# Schematic_V0_3.net
KiCad netlist of a schematic drawn in EAGLE
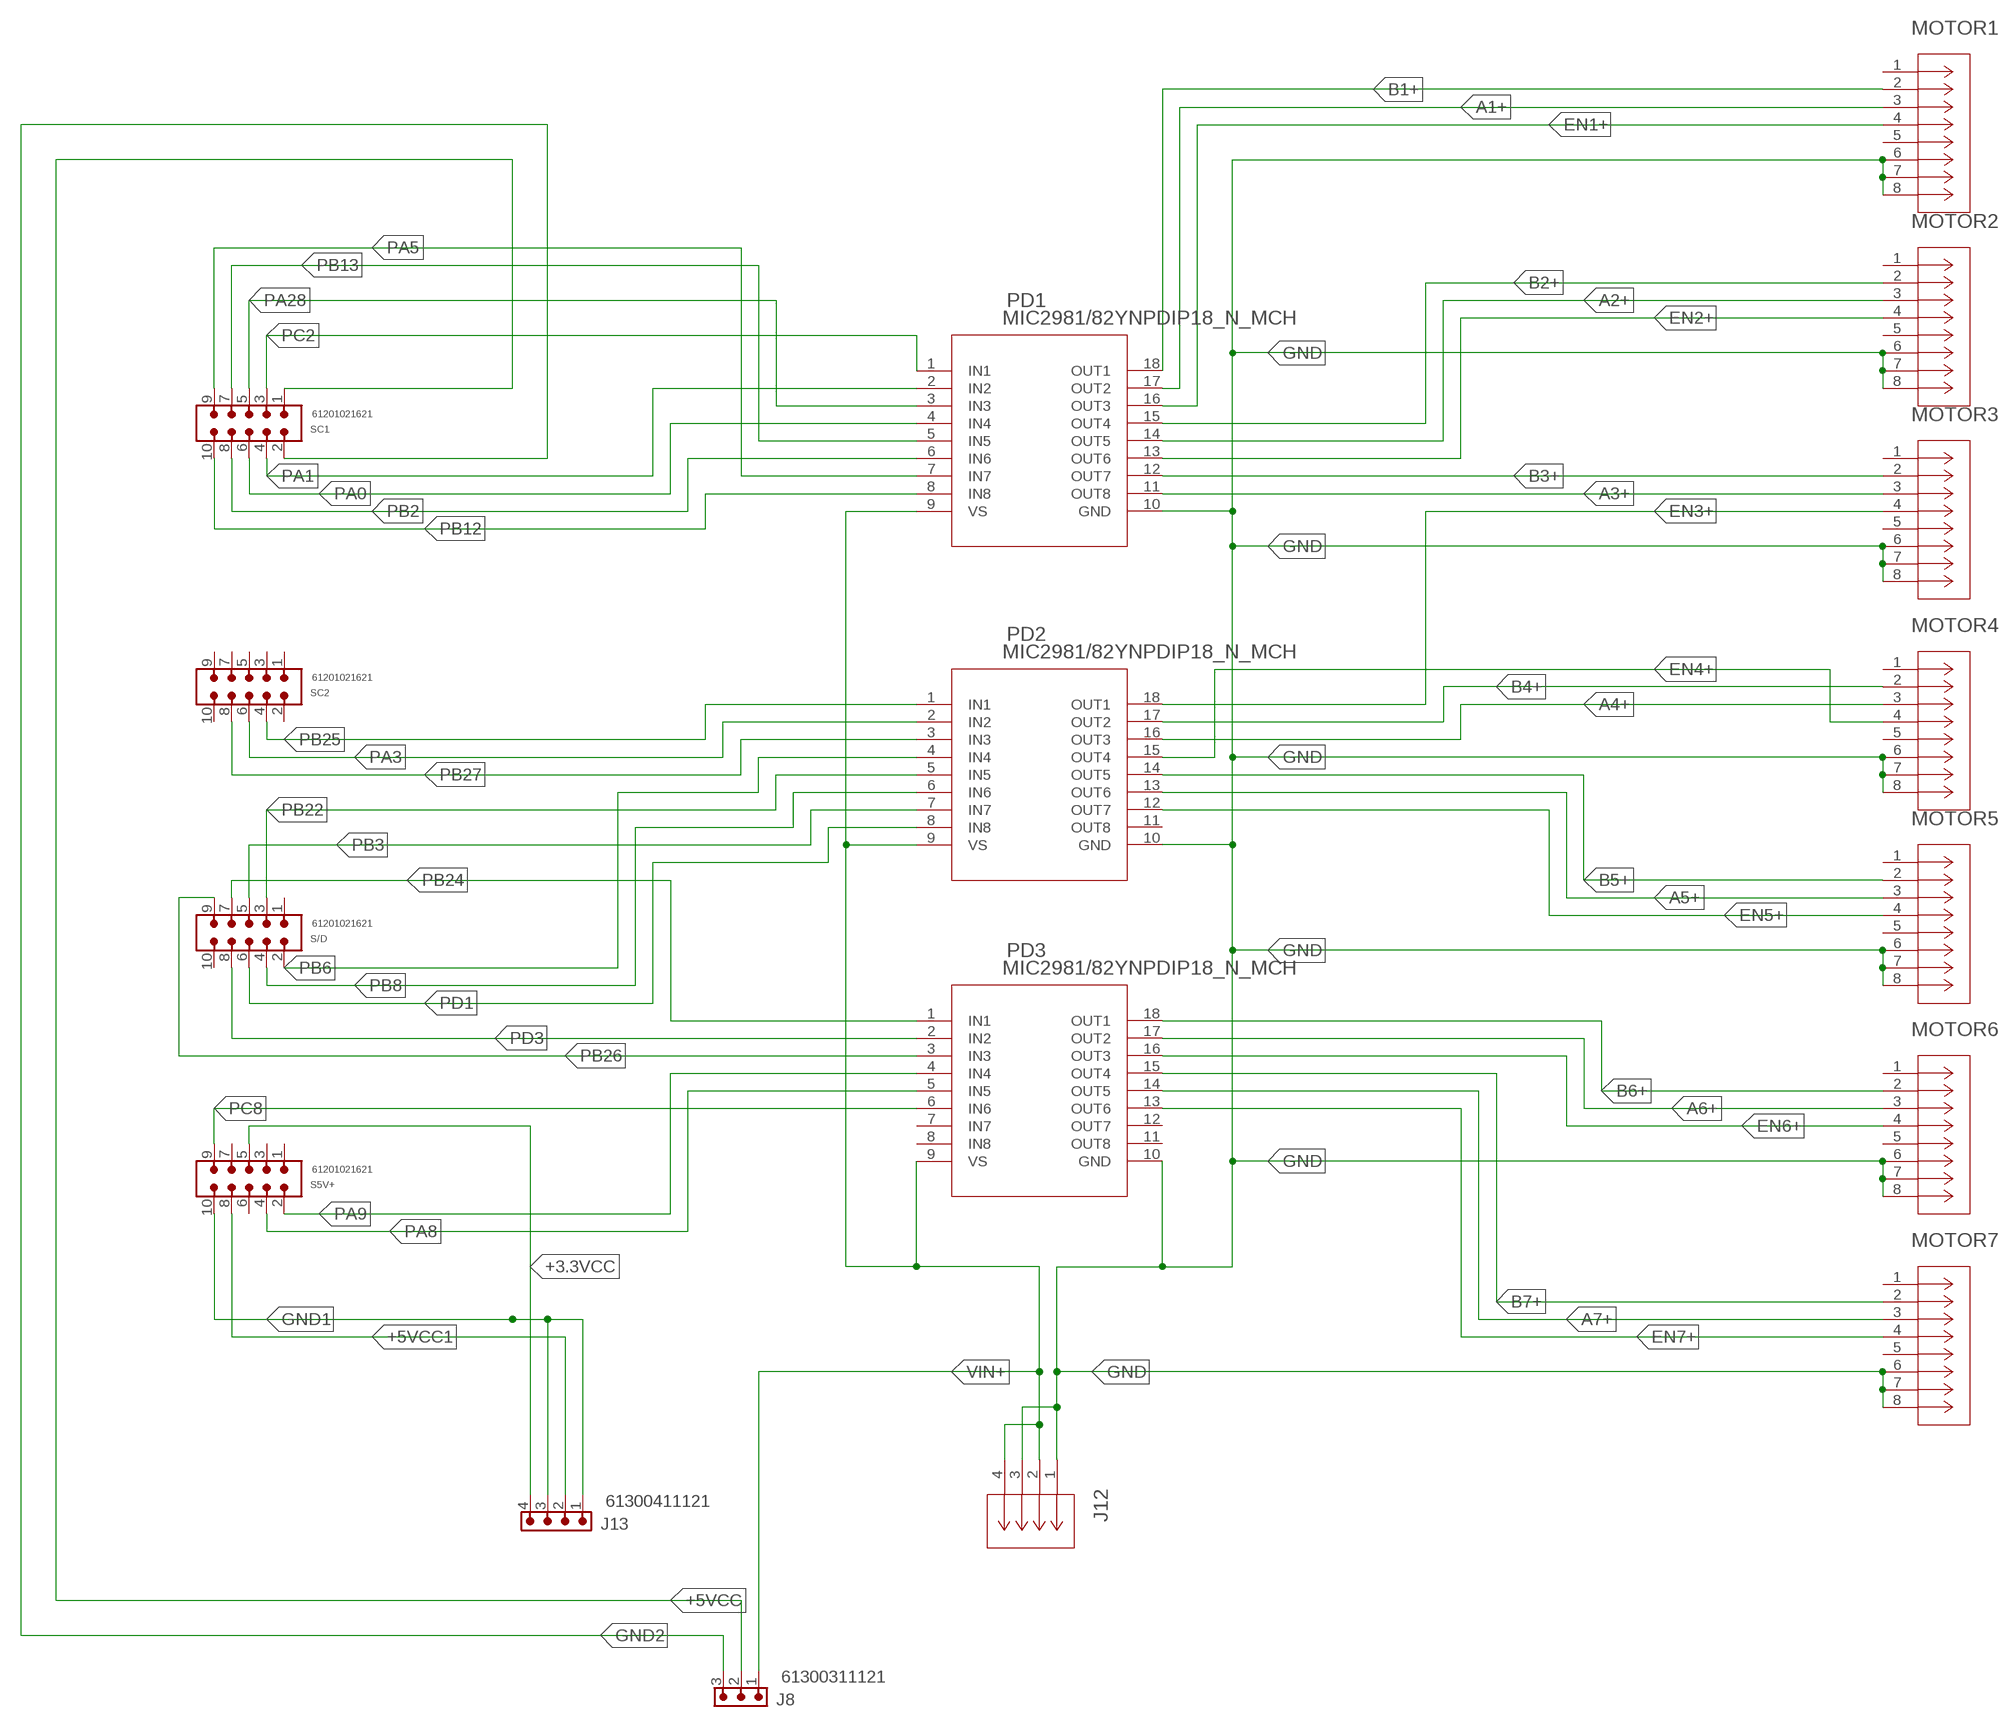
[diagram p0: schematic, sheet 1]

(export (version "E")
  (design (tool "Eeschema 10.0.6"))
  (components
    (comp (ref "J8")
      (value "61300311121")
      (footprint "eagle-import:61300311121")
      (libsource (lib "eagle-import") (part "6130XX11121_61300311121"))
    )
    (comp (ref "J12")
      (value "YK3310403000GCONN_YK331040XX00G_AMP")
      (footprint "eagle-import:CONN_YK331040XX00G_AMP")
      (fields
        (field (name "MANUFACTURER_PART_NUMBER") "YK3310403000G")
        (field (name "COPYRIGHT") "Copyright (C) 2024 Ultra Librarian. All rights reserved.")
      )
      (libsource (lib "eagle-import") (part "YK3310403000GCONN_YK331040XX00G_AMP"))
    )
    (comp (ref "J13")
      (value "61300411121")
      (footprint "eagle-import:61300411121")
      (libsource (lib "eagle-import") (part "6130XX11121_61300411121"))
    )
    (comp (ref "MOTOR1")
      (value "1724470208CON_1724470208")
      (footprint "eagle-import:CON_1724470208")
      (fields
        (field (name "MANUFACTURER_PART_NUMBER") "1724470208")
        (field (name "COPYRIGHT") "Copyright (C) 2024 Ultra Librarian. All rights reserved.")
      )
      (libsource (lib "eagle-import") (part "1724470208CON_1724470208"))
    )
    (comp (ref "MOTOR2")
      (value "1724470208CON_1724470208")
      (footprint "eagle-import:CON_1724470208")
      (fields
        (field (name "MANUFACTURER_PART_NUMBER") "1724470208")
        (field (name "COPYRIGHT") "Copyright (C) 2024 Ultra Librarian. All rights reserved.")
      )
      (libsource (lib "eagle-import") (part "1724470208CON_1724470208"))
    )
    (comp (ref "MOTOR3")
      (value "1724470208CON_1724470208")
      (footprint "eagle-import:CON_1724470208")
      (fields
        (field (name "MANUFACTURER_PART_NUMBER") "1724470208")
        (field (name "COPYRIGHT") "Copyright (C) 2024 Ultra Librarian. All rights reserved.")
      )
      (libsource (lib "eagle-import") (part "1724470208CON_1724470208"))
    )
    (comp (ref "MOTOR4")
      (value "1724470208CON_1724470208")
      (footprint "eagle-import:CON_1724470208")
      (fields
        (field (name "MANUFACTURER_PART_NUMBER") "1724470208")
        (field (name "COPYRIGHT") "Copyright (C) 2024 Ultra Librarian. All rights reserved.")
      )
      (libsource (lib "eagle-import") (part "1724470208CON_1724470208"))
    )
    (comp (ref "MOTOR5")
      (value "1724470208CON_1724470208")
      (footprint "eagle-import:CON_1724470208")
      (fields
        (field (name "MANUFACTURER_PART_NUMBER") "1724470208")
        (field (name "COPYRIGHT") "Copyright (C) 2024 Ultra Librarian. All rights reserved.")
      )
      (libsource (lib "eagle-import") (part "1724470208CON_1724470208"))
    )
    (comp (ref "MOTOR6")
      (value "1724470208CON_1724470208")
      (footprint "eagle-import:CON_1724470208")
      (fields
        (field (name "MANUFACTURER_PART_NUMBER") "1724470208")
        (field (name "COPYRIGHT") "Copyright (C) 2024 Ultra Librarian. All rights reserved.")
      )
      (libsource (lib "eagle-import") (part "1724470208CON_1724470208"))
    )
    (comp (ref "MOTOR7")
      (value "1724470208CON_1724470208")
      (footprint "eagle-import:CON_1724470208")
      (fields
        (field (name "MANUFACTURER_PART_NUMBER") "1724470208")
        (field (name "COPYRIGHT") "Copyright (C) 2024 Ultra Librarian. All rights reserved.")
      )
      (libsource (lib "eagle-import") (part "1724470208CON_1724470208"))
    )
    (comp (ref "PD1")
      (value "MIC2981/82YNPDIP18_N_MCH")
      (footprint "eagle-import:PDIP18_N_MCH")
      (fields
        (field (name "MANUFACTURER_PART_NUMBER") "MIC2981/82YN")
        (field (name "COPYRIGHT") "Copyright (C) 2024 Ultra Librarian. All rights reserved.")
      )
      (libsource (lib "eagle-import") (part "MIC2981/82YNPDIP18_N_MCH"))
    )
    (comp (ref "PD2")
      (value "MIC2981/82YNPDIP18_N_MCH")
      (footprint "eagle-import:PDIP18_N_MCH")
      (fields
        (field (name "MANUFACTURER_PART_NUMBER") "MIC2981/82YN")
        (field (name "COPYRIGHT") "Copyright (C) 2024 Ultra Librarian. All rights reserved.")
      )
      (libsource (lib "eagle-import") (part "MIC2981/82YNPDIP18_N_MCH"))
    )
    (comp (ref "PD3")
      (value "MIC2981/82YNPDIP18_N_MCH")
      (footprint "eagle-import:PDIP18_N_MCH")
      (fields
        (field (name "MANUFACTURER_PART_NUMBER") "MIC2981/82YN")
        (field (name "COPYRIGHT") "Copyright (C) 2024 Ultra Librarian. All rights reserved.")
      )
      (libsource (lib "eagle-import") (part "MIC2981/82YNPDIP18_N_MCH"))
    )
    (comp (ref "S/D")
      (value "61201021621")
      (footprint "eagle-import:61201021621")
      (libsource (lib "eagle-import") (part "6120XX21621_61201021621"))
    )
    (comp (ref "S5V+")
      (value "61201021621")
      (footprint "eagle-import:61201021621")
      (libsource (lib "eagle-import") (part "6120XX21621_61201021621"))
    )
    (comp (ref "SC1")
      (value "61201021621")
      (footprint "eagle-import:61201021621")
      (libsource (lib "eagle-import") (part "6120XX21621_61201021621"))
    )
    (comp (ref "SC2")
      (value "61201021621")
      (footprint "eagle-import:61201021621")
      (libsource (lib "eagle-import") (part "6120XX21621_61201021621"))
    )
  )
  (nets
    (net (code "1") (name "+3.3VCC") (class "Default")
      (node (ref "J13") (pin "4") (pinfunction "4_4") (pintype "passive"))
      (node (ref "S5V+") (pin "5") (pinfunction "5_5") (pintype "passive"))
    )
    (net (code "2") (name "+5VCC") (class "Default")
      (node (ref "J8") (pin "2") (pinfunction "2_2") (pintype "passive"))
      (node (ref "SC1") (pin "1") (pinfunction "1_1") (pintype "passive"))
    )
    (net (code "3") (name "+5VCC1") (class "Default")
      (node (ref "J13") (pin "2") (pinfunction "2_2") (pintype "passive"))
      (node (ref "S5V+") (pin "8") (pinfunction "8_8") (pintype "passive"))
    )
    (net (code "4") (name "A1+") (class "Default")
      (node (ref "MOTOR1") (pin "3") (pinfunction "3_3") (pintype "passive"))
      (node (ref "PD1") (pin "17") (pinfunction "OUT2_17") (pintype "output"))
    )
    (net (code "5") (name "A2+") (class "Default")
      (node (ref "MOTOR2") (pin "3") (pinfunction "3_3") (pintype "passive"))
      (node (ref "PD1") (pin "14") (pinfunction "OUT5_14") (pintype "output"))
    )
    (net (code "6") (name "A3+") (class "Default")
      (node (ref "MOTOR3") (pin "3") (pinfunction "3_3") (pintype "passive"))
      (node (ref "PD1") (pin "11") (pinfunction "OUT8_11") (pintype "output"))
    )
    (net (code "7") (name "A4+") (class "Default")
      (node (ref "MOTOR4") (pin "3") (pinfunction "3_3") (pintype "passive"))
      (node (ref "PD2") (pin "16") (pinfunction "OUT3_16") (pintype "output"))
    )
    (net (code "8") (name "A5+") (class "Default")
      (node (ref "MOTOR5") (pin "3") (pinfunction "3_3") (pintype "passive"))
      (node (ref "PD2") (pin "13") (pinfunction "OUT6_13") (pintype "output"))
    )
    (net (code "9") (name "A6+") (class "Default")
      (node (ref "MOTOR6") (pin "3") (pinfunction "3_3") (pintype "passive"))
      (node (ref "PD3") (pin "17") (pinfunction "OUT2_17") (pintype "output"))
    )
    (net (code "10") (name "A7+") (class "Default")
      (node (ref "MOTOR7") (pin "3") (pinfunction "3_3") (pintype "passive"))
      (node (ref "PD3") (pin "14") (pinfunction "OUT5_14") (pintype "output"))
    )
    (net (code "11") (name "B1+") (class "Default")
      (node (ref "MOTOR1") (pin "2") (pinfunction "2_2") (pintype "passive"))
      (node (ref "PD1") (pin "18") (pinfunction "OUT1_18") (pintype "output"))
    )
    (net (code "12") (name "B2+") (class "Default")
      (node (ref "MOTOR2") (pin "2") (pinfunction "2_2") (pintype "passive"))
      (node (ref "PD1") (pin "15") (pinfunction "OUT4_15") (pintype "output"))
    )
    (net (code "13") (name "B3+") (class "Default")
      (node (ref "MOTOR3") (pin "2") (pinfunction "2_2") (pintype "passive"))
      (node (ref "PD1") (pin "12") (pinfunction "OUT7_12") (pintype "output"))
    )
    (net (code "14") (name "B4+") (class "Default")
      (node (ref "MOTOR4") (pin "2") (pinfunction "2_2") (pintype "passive"))
      (node (ref "PD2") (pin "17") (pinfunction "OUT2_17") (pintype "output"))
    )
    (net (code "15") (name "B5+") (class "Default")
      (node (ref "MOTOR5") (pin "2") (pinfunction "2_2") (pintype "passive"))
      (node (ref "PD2") (pin "14") (pinfunction "OUT5_14") (pintype "output"))
    )
    (net (code "16") (name "B6+") (class "Default")
      (node (ref "MOTOR6") (pin "2") (pinfunction "2_2") (pintype "passive"))
      (node (ref "PD3") (pin "18") (pinfunction "OUT1_18") (pintype "output"))
    )
    (net (code "17") (name "B7+") (class "Default")
      (node (ref "MOTOR7") (pin "2") (pinfunction "2_2") (pintype "passive"))
      (node (ref "PD3") (pin "15") (pinfunction "OUT4_15") (pintype "output"))
    )
    (net (code "18") (name "EN1+") (class "Default")
      (node (ref "MOTOR1") (pin "4") (pinfunction "4_4") (pintype "passive"))
      (node (ref "PD1") (pin "16") (pinfunction "OUT3_16") (pintype "output"))
    )
    (net (code "19") (name "EN2+") (class "Default")
      (node (ref "MOTOR2") (pin "4") (pinfunction "4_4") (pintype "passive"))
      (node (ref "PD1") (pin "13") (pinfunction "OUT6_13") (pintype "output"))
    )
    (net (code "20") (name "EN3+") (class "Default")
      (node (ref "MOTOR3") (pin "4") (pinfunction "4_4") (pintype "passive"))
      (node (ref "PD2") (pin "18") (pinfunction "OUT1_18") (pintype "output"))
    )
    (net (code "21") (name "EN4+") (class "Default")
      (node (ref "MOTOR4") (pin "4") (pinfunction "4_4") (pintype "passive"))
      (node (ref "PD2") (pin "15") (pinfunction "OUT4_15") (pintype "output"))
    )
    (net (code "22") (name "EN5+") (class "Default")
      (node (ref "MOTOR5") (pin "4") (pinfunction "4_4") (pintype "passive"))
      (node (ref "PD2") (pin "12") (pinfunction "OUT7_12") (pintype "output"))
    )
    (net (code "23") (name "EN6+") (class "Default")
      (node (ref "MOTOR6") (pin "4") (pinfunction "4_4") (pintype "passive"))
      (node (ref "PD3") (pin "16") (pinfunction "OUT3_16") (pintype "output"))
    )
    (net (code "24") (name "EN7+") (class "Default")
      (node (ref "MOTOR7") (pin "4") (pinfunction "4_4") (pintype "passive"))
      (node (ref "PD3") (pin "13") (pinfunction "OUT6_13") (pintype "output"))
    )
    (net (code "25") (name "GND") (class "Default")
      (node (ref "J12") (pin "1") (pinfunction "1_1") (pintype "passive"))
      (node (ref "J12") (pin "3") (pinfunction "3_3") (pintype "passive"))
      (node (ref "MOTOR1") (pin "6") (pinfunction "6_6") (pintype "passive"))
      (node (ref "MOTOR1") (pin "7") (pinfunction "7_7") (pintype "passive"))
      (node (ref "MOTOR1") (pin "8") (pinfunction "8_8") (pintype "passive"))
      (node (ref "MOTOR2") (pin "6") (pinfunction "6_6") (pintype "passive"))
      (node (ref "MOTOR2") (pin "7") (pinfunction "7_7") (pintype "passive"))
      (node (ref "MOTOR2") (pin "8") (pinfunction "8_8") (pintype "passive"))
      (node (ref "MOTOR3") (pin "6") (pinfunction "6_6") (pintype "passive"))
      (node (ref "MOTOR3") (pin "7") (pinfunction "7_7") (pintype "passive"))
      (node (ref "MOTOR3") (pin "8") (pinfunction "8_8") (pintype "passive"))
      (node (ref "MOTOR4") (pin "6") (pinfunction "6_6") (pintype "passive"))
      (node (ref "MOTOR4") (pin "7") (pinfunction "7_7") (pintype "passive"))
      (node (ref "MOTOR4") (pin "8") (pinfunction "8_8") (pintype "passive"))
      (node (ref "MOTOR5") (pin "6") (pinfunction "6_6") (pintype "passive"))
      (node (ref "MOTOR5") (pin "7") (pinfunction "7_7") (pintype "passive"))
      (node (ref "MOTOR5") (pin "8") (pinfunction "8_8") (pintype "passive"))
      (node (ref "MOTOR6") (pin "6") (pinfunction "6_6") (pintype "passive"))
      (node (ref "MOTOR6") (pin "7") (pinfunction "7_7") (pintype "passive"))
      (node (ref "MOTOR6") (pin "8") (pinfunction "8_8") (pintype "passive"))
      (node (ref "MOTOR7") (pin "6") (pinfunction "6_6") (pintype "passive"))
      (node (ref "MOTOR7") (pin "7") (pinfunction "7_7") (pintype "passive"))
      (node (ref "MOTOR7") (pin "8") (pinfunction "8_8") (pintype "passive"))
      (node (ref "PD1") (pin "10") (pinfunction "GND_10") (pintype "passive"))
      (node (ref "PD2") (pin "10") (pinfunction "GND_10") (pintype "passive"))
      (node (ref "PD3") (pin "10") (pinfunction "GND_10") (pintype "passive"))
    )
    (net (code "26") (name "GND1") (class "Default")
      (node (ref "J13") (pin "1") (pinfunction "1_1") (pintype "passive"))
      (node (ref "J13") (pin "3") (pinfunction "3_3") (pintype "passive"))
      (node (ref "S5V+") (pin "10") (pinfunction "10_10") (pintype "passive"))
    )
    (net (code "27") (name "GND2") (class "Default")
      (node (ref "J8") (pin "3") (pinfunction "3_3") (pintype "passive"))
      (node (ref "SC1") (pin "2") (pinfunction "2_2") (pintype "passive"))
    )
    (net (code "28") (name "PA0") (class "Default")
      (node (ref "PD1") (pin "4") (pinfunction "IN4_4") (pintype "input"))
      (node (ref "SC1") (pin "6") (pinfunction "6_6") (pintype "passive"))
    )
    (net (code "29") (name "PA1") (class "Default")
      (node (ref "PD1") (pin "2") (pinfunction "IN2_2") (pintype "input"))
      (node (ref "SC1") (pin "4") (pinfunction "4_4") (pintype "passive"))
    )
    (net (code "30") (name "PA3") (class "Default")
      (node (ref "PD2") (pin "2") (pinfunction "IN2_2") (pintype "input"))
      (node (ref "SC2") (pin "6") (pinfunction "6_6") (pintype "passive"))
    )
    (net (code "31") (name "PA5") (class "Default")
      (node (ref "PD1") (pin "7") (pinfunction "IN7_7") (pintype "input"))
      (node (ref "SC1") (pin "9") (pinfunction "9_9") (pintype "passive"))
    )
    (net (code "32") (name "PA8") (class "Default")
      (node (ref "PD3") (pin "5") (pinfunction "IN5_5") (pintype "input"))
      (node (ref "S5V+") (pin "4") (pinfunction "4_4") (pintype "passive"))
    )
    (net (code "33") (name "PA9") (class "Default")
      (node (ref "PD3") (pin "4") (pinfunction "IN4_4") (pintype "input"))
      (node (ref "S5V+") (pin "2") (pinfunction "2_2") (pintype "passive"))
    )
    (net (code "34") (name "PA28") (class "Default")
      (node (ref "PD1") (pin "3") (pinfunction "IN3_3") (pintype "input"))
      (node (ref "SC1") (pin "5") (pinfunction "5_5") (pintype "passive"))
    )
    (net (code "35") (name "PB2") (class "Default")
      (node (ref "PD1") (pin "6") (pinfunction "IN6_6") (pintype "input"))
      (node (ref "SC1") (pin "8") (pinfunction "8_8") (pintype "passive"))
    )
    (net (code "36") (name "PB3") (class "Default")
      (node (ref "PD2") (pin "7") (pinfunction "IN7_7") (pintype "input"))
      (node (ref "S/D") (pin "5") (pinfunction "5_5") (pintype "passive"))
    )
    (net (code "37") (name "PB6") (class "Default")
      (node (ref "PD2") (pin "4") (pinfunction "IN4_4") (pintype "input"))
      (node (ref "S/D") (pin "2") (pinfunction "2_2") (pintype "passive"))
    )
    (net (code "38") (name "PB8") (class "Default")
      (node (ref "PD2") (pin "6") (pinfunction "IN6_6") (pintype "input"))
      (node (ref "S/D") (pin "4") (pinfunction "4_4") (pintype "passive"))
    )
    (net (code "39") (name "PB12") (class "Default")
      (node (ref "PD1") (pin "8") (pinfunction "IN8_8") (pintype "input"))
      (node (ref "SC1") (pin "10") (pinfunction "10_10") (pintype "passive"))
    )
    (net (code "40") (name "PB13") (class "Default")
      (node (ref "PD1") (pin "5") (pinfunction "IN5_5") (pintype "input"))
      (node (ref "SC1") (pin "7") (pinfunction "7_7") (pintype "passive"))
    )
    (net (code "41") (name "PB22") (class "Default")
      (node (ref "PD2") (pin "5") (pinfunction "IN5_5") (pintype "input"))
      (node (ref "S/D") (pin "3") (pinfunction "3_3") (pintype "passive"))
    )
    (net (code "42") (name "PB24") (class "Default")
      (node (ref "PD3") (pin "1") (pinfunction "IN1_1") (pintype "input"))
      (node (ref "S/D") (pin "7") (pinfunction "7_7") (pintype "passive"))
    )
    (net (code "43") (name "PB25") (class "Default")
      (node (ref "PD2") (pin "1") (pinfunction "IN1_1") (pintype "input"))
      (node (ref "SC2") (pin "4") (pinfunction "4_4") (pintype "passive"))
    )
    (net (code "44") (name "PB26") (class "Default")
      (node (ref "PD3") (pin "3") (pinfunction "IN3_3") (pintype "input"))
      (node (ref "S/D") (pin "9") (pinfunction "9_9") (pintype "passive"))
    )
    (net (code "45") (name "PB27") (class "Default")
      (node (ref "PD2") (pin "3") (pinfunction "IN3_3") (pintype "input"))
      (node (ref "SC2") (pin "8") (pinfunction "8_8") (pintype "passive"))
    )
    (net (code "46") (name "PC2") (class "Default")
      (node (ref "PD1") (pin "1") (pinfunction "IN1_1") (pintype "input"))
      (node (ref "SC1") (pin "3") (pinfunction "3_3") (pintype "passive"))
    )
    (net (code "47") (name "PC8") (class "Default")
      (node (ref "PD3") (pin "6") (pinfunction "IN6_6") (pintype "input"))
      (node (ref "S5V+") (pin "9") (pinfunction "9_9") (pintype "passive"))
    )
    (net (code "48") (name "PD1") (class "Default")
      (node (ref "PD2") (pin "8") (pinfunction "IN8_8") (pintype "input"))
      (node (ref "S/D") (pin "6") (pinfunction "6_6") (pintype "passive"))
    )
    (net (code "49") (name "PD3") (class "Default")
      (node (ref "PD3") (pin "2") (pinfunction "IN2_2") (pintype "input"))
      (node (ref "S/D") (pin "8") (pinfunction "8_8") (pintype "passive"))
    )
    (net (code "50") (name "VIN+") (class "Default")
      (node (ref "J12") (pin "2") (pinfunction "2_2") (pintype "passive"))
      (node (ref "J12") (pin "4") (pinfunction "4_4") (pintype "passive"))
      (node (ref "J8") (pin "1") (pinfunction "1_1") (pintype "passive"))
      (node (ref "PD1") (pin "9") (pinfunction "VS_9") (pintype "power_in"))
      (node (ref "PD2") (pin "9") (pinfunction "VS_9") (pintype "power_in"))
      (node (ref "PD3") (pin "9") (pinfunction "VS_9") (pintype "power_in"))
    )
    (net (code "51") (name "unconnected-(MOTOR1-Pad1)") (class "Default")
      (node (ref "MOTOR1") (pin "1") (pinfunction "1_1") (pintype "passive"))
    )
    (net (code "52") (name "unconnected-(MOTOR1-Pad5)") (class "Default")
      (node (ref "MOTOR1") (pin "5") (pinfunction "5_5") (pintype "passive"))
    )
    (net (code "53") (name "unconnected-(MOTOR2-Pad1)") (class "Default")
      (node (ref "MOTOR2") (pin "1") (pinfunction "1_1") (pintype "passive"))
    )
    (net (code "54") (name "unconnected-(MOTOR2-Pad5)") (class "Default")
      (node (ref "MOTOR2") (pin "5") (pinfunction "5_5") (pintype "passive"))
    )
    (net (code "55") (name "unconnected-(MOTOR3-Pad1)") (class "Default")
      (node (ref "MOTOR3") (pin "1") (pinfunction "1_1") (pintype "passive"))
    )
    (net (code "56") (name "unconnected-(MOTOR3-Pad5)") (class "Default")
      (node (ref "MOTOR3") (pin "5") (pinfunction "5_5") (pintype "passive"))
    )
    (net (code "57") (name "unconnected-(MOTOR4-Pad1)") (class "Default")
      (node (ref "MOTOR4") (pin "1") (pinfunction "1_1") (pintype "passive"))
    )
    (net (code "58") (name "unconnected-(MOTOR4-Pad5)") (class "Default")
      (node (ref "MOTOR4") (pin "5") (pinfunction "5_5") (pintype "passive"))
    )
    (net (code "59") (name "unconnected-(MOTOR5-Pad1)") (class "Default")
      (node (ref "MOTOR5") (pin "1") (pinfunction "1_1") (pintype "passive"))
    )
    (net (code "60") (name "unconnected-(MOTOR5-Pad5)") (class "Default")
      (node (ref "MOTOR5") (pin "5") (pinfunction "5_5") (pintype "passive"))
    )
    (net (code "61") (name "unconnected-(MOTOR6-Pad1)") (class "Default")
      (node (ref "MOTOR6") (pin "1") (pinfunction "1_1") (pintype "passive"))
    )
    (net (code "62") (name "unconnected-(MOTOR6-Pad5)") (class "Default")
      (node (ref "MOTOR6") (pin "5") (pinfunction "5_5") (pintype "passive"))
    )
    (net (code "63") (name "unconnected-(MOTOR7-Pad1)") (class "Default")
      (node (ref "MOTOR7") (pin "1") (pinfunction "1_1") (pintype "passive"))
    )
    (net (code "64") (name "unconnected-(MOTOR7-Pad5)") (class "Default")
      (node (ref "MOTOR7") (pin "5") (pinfunction "5_5") (pintype "passive"))
    )
    (net (code "65") (name "unconnected-(PD2-OUT8-Pad11)") (class "Default")
      (node (ref "PD2") (pin "11") (pinfunction "OUT8_11") (pintype "output"))
    )
    (net (code "66") (name "unconnected-(PD3-IN7-Pad7)") (class "Default")
      (node (ref "PD3") (pin "7") (pinfunction "IN7_7") (pintype "input"))
    )
    (net (code "67") (name "unconnected-(PD3-IN8-Pad8)") (class "Default")
      (node (ref "PD3") (pin "8") (pinfunction "IN8_8") (pintype "input"))
    )
    (net (code "68") (name "unconnected-(PD3-OUT7-Pad12)") (class "Default")
      (node (ref "PD3") (pin "12") (pinfunction "OUT7_12") (pintype "output"))
    )
    (net (code "69") (name "unconnected-(PD3-OUT8-Pad11)") (class "Default")
      (node (ref "PD3") (pin "11") (pinfunction "OUT8_11") (pintype "output"))
    )
    (net (code "70") (name "unconnected-(S/D-Pad1)") (class "Default")
      (node (ref "S/D") (pin "1") (pinfunction "1_1") (pintype "passive"))
    )
    (net (code "71") (name "unconnected-(S/D-Pad10)") (class "Default")
      (node (ref "S/D") (pin "10") (pinfunction "10_10") (pintype "passive"))
    )
    (net (code "72") (name "unconnected-(S5V+-Pad1)") (class "Default")
      (node (ref "S5V+") (pin "1") (pinfunction "1_1") (pintype "passive"))
    )
    (net (code "73") (name "unconnected-(S5V+-Pad3)") (class "Default")
      (node (ref "S5V+") (pin "3") (pinfunction "3_3") (pintype "passive"))
    )
    (net (code "74") (name "unconnected-(S5V+-Pad6)") (class "Default")
      (node (ref "S5V+") (pin "6") (pinfunction "6_6") (pintype "passive"))
    )
    (net (code "75") (name "unconnected-(S5V+-Pad7)") (class "Default")
      (node (ref "S5V+") (pin "7") (pinfunction "7_7") (pintype "passive"))
    )
    (net (code "76") (name "unconnected-(SC2-Pad1)") (class "Default")
      (node (ref "SC2") (pin "1") (pinfunction "1_1") (pintype "passive"))
    )
    (net (code "77") (name "unconnected-(SC2-Pad2)") (class "Default")
      (node (ref "SC2") (pin "2") (pinfunction "2_2") (pintype "passive"))
    )
    (net (code "78") (name "unconnected-(SC2-Pad3)") (class "Default")
      (node (ref "SC2") (pin "3") (pinfunction "3_3") (pintype "passive"))
    )
    (net (code "79") (name "unconnected-(SC2-Pad5)") (class "Default")
      (node (ref "SC2") (pin "5") (pinfunction "5_5") (pintype "passive"))
    )
    (net (code "80") (name "unconnected-(SC2-Pad7)") (class "Default")
      (node (ref "SC2") (pin "7") (pinfunction "7_7") (pintype "passive"))
    )
    (net (code "81") (name "unconnected-(SC2-Pad9)") (class "Default")
      (node (ref "SC2") (pin "9") (pinfunction "9_9") (pintype "passive"))
    )
    (net (code "82") (name "unconnected-(SC2-Pad10)") (class "Default")
      (node (ref "SC2") (pin "10") (pinfunction "10_10") (pintype "passive"))
    )
  )
)
